# schottky.net
KiCad netlist of a schematic drawn in EAGLE
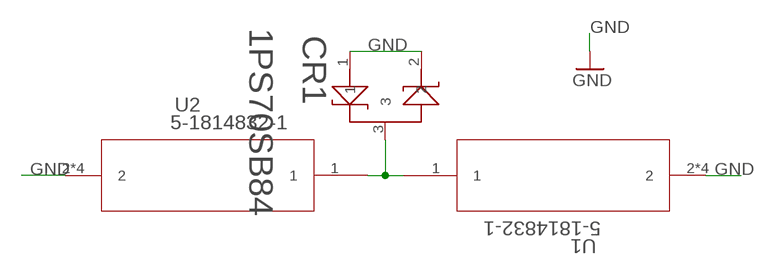
[diagram p0: schematic, sheet 1]

(export (version "E")
  (design (tool "Eeschema 10.0.6"))
  (components
    (comp (ref "CR1")
      (value "1PS70SB84")
      (footprint "eagle-import:SOT323")
      (fields (field (name "COPYRIGHT") "Copyright (C) 2015 Accelerated Designs. All rights reserved"))
      (libsource (lib "eagle-import") (part "1PS70SB84"))
    )
    (comp (ref "U1")
      (value "5-1814832-1")
      (footprint "eagle-import:5-1814832-1")
      (fields (field (name "COPYRIGHT") "Copyright (C) 2015 Accelerated Designs. All rights reserved"))
      (libsource (lib "eagle-import") (part "5-1814832-1"))
    )
    (comp (ref "U2")
      (value "5-1814832-1")
      (footprint "eagle-import:5-1814832-1")
      (fields (field (name "COPYRIGHT") "Copyright (C) 2015 Accelerated Designs. All rights reserved"))
      (libsource (lib "eagle-import") (part "5-1814832-1"))
    )
  )
  (nets
    (net (code "1") (name "GND") (class "Default")
      (node (ref "CR1") (pin "1") (pinfunction "1_1") (pintype "passive"))
      (node (ref "CR1") (pin "2") (pinfunction "2_2") (pintype "passive"))
      (node (ref "U1") (pin "2") (pinfunction "2_2") (pintype "bidirectional"))
      (node (ref "U1") (pin "3") (pinfunction "2_3") (pintype "bidirectional"))
      (node (ref "U1") (pin "4") (pinfunction "2_4") (pintype "bidirectional"))
      (node (ref "U1") (pin "5") (pinfunction "2_5") (pintype "bidirectional"))
      (node (ref "U2") (pin "2") (pinfunction "2_2") (pintype "bidirectional"))
      (node (ref "U2") (pin "3") (pinfunction "2_3") (pintype "bidirectional"))
      (node (ref "U2") (pin "4") (pinfunction "2_4") (pintype "bidirectional"))
      (node (ref "U2") (pin "5") (pinfunction "2_5") (pintype "bidirectional"))
    )
    (net (code "2") (name "Net-(CR1-Pad3)") (class "Default")
      (node (ref "CR1") (pin "3") (pinfunction "3_3") (pintype "passive"))
      (node (ref "U1") (pin "1") (pinfunction "1_1") (pintype "passive"))
      (node (ref "U2") (pin "1") (pinfunction "1_1") (pintype "passive"))
    )
  )
)
